# etc.net
KiCad netlist of a schematic drawn in Altium Designer
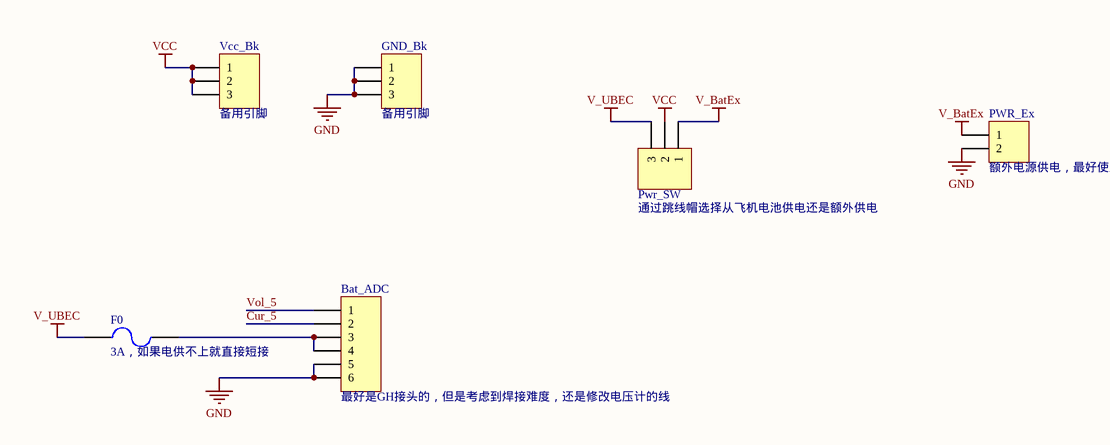
[diagram p0: etc.SchDoc]

(export (version "E")
  (design (tool "Eeschema 10.0.6"))
  (components
    (comp (ref "Bat_ADC")
      (value "最好是GH接头的，但是考虑到焊接难度，还是修改电压计的线")
      (footprint "HDR1X6")
      (description "Header, 6-Pin")
      (fields (field (name "PUBLISHER") "Altium Limited"))
      (libsource (lib "Miscellaneous Connectors") (part "Header 6"))
    )
    (comp (ref "F0")
      (value "3A，如果电供不上就直接短接")
      (footprint "Miscellaneous Devices:1812")
      (description "Fuse")
      (fields (field (name "PUBLISHER") "Altium Limited"))
      (libsource (lib "Miscellaneous Devices") (part "Fuse 2"))
    )
    (comp (ref "GND_Bk")
      (value "备用引脚")
      (footprint "HDR1X3")
      (description "Header, 3-Pin")
      (fields (field (name "PUBLISHER") "Altium Limited"))
      (libsource (lib "Miscellaneous Connectors") (part "Header 3"))
    )
    (comp (ref "PWR_Ex")
      (value "额外电源供电，最好使用接线端子")
      (footprint "HDR1X2")
      (description "Header, 2-Pin")
      (fields (field (name "PUBLISHER") "Altium Limited"))
      (libsource (lib "Miscellaneous Connectors") (part "Header 2"))
    )
    (comp (ref "Pwr_SW")
      (value "通过跳线帽选择从飞机电池供电还是额外供电")
      (footprint "HDR1X3")
      (description "Header, 3-Pin")
      (fields (field (name "PUBLISHER") "Altium Limited"))
      (libsource (lib "") (part "Header 3_1"))
    )
    (comp (ref "Vcc_Bk")
      (value "备用引脚")
      (footprint "HDR1X3")
      (description "Header, 3-Pin")
      (fields (field (name "PUBLISHER") "Altium Limited"))
      (libsource (lib "Miscellaneous Connectors") (part "Header 3"))
    )
  )
  (nets
    (net (code "1") (name "/Cur_5") (class "Default")
      (node (ref "Bat_ADC") (pin "2") (pinfunction "2_2") (pintype "passive"))
    )
    (net (code "2") (name "/Vol_5") (class "Default")
      (node (ref "Bat_ADC") (pin "1") (pinfunction "1_1") (pintype "passive"))
    )
    (net (code "3") (name "GND") (class "Default")
      (node (ref "Bat_ADC") (pin "5") (pinfunction "5_5") (pintype "passive"))
      (node (ref "Bat_ADC") (pin "6") (pinfunction "6_6") (pintype "passive"))
      (node (ref "GND_Bk") (pin "1") (pinfunction "1_1") (pintype "passive"))
      (node (ref "GND_Bk") (pin "2") (pinfunction "2_2") (pintype "passive"))
      (node (ref "GND_Bk") (pin "3") (pinfunction "3_3") (pintype "passive"))
      (node (ref "PWR_Ex") (pin "2") (pinfunction "2_2") (pintype "passive"))
    )
    (net (code "4") (name "Net-(Bat_ADC-Pad3)") (class "Default")
      (node (ref "Bat_ADC") (pin "3") (pinfunction "3_3") (pintype "passive"))
      (node (ref "Bat_ADC") (pin "4") (pinfunction "4_4") (pintype "passive"))
      (node (ref "F0") (pin "2") (pinfunction "2_2") (pintype "passive"))
    )
    (net (code "5") (name "VCC") (class "Default")
      (node (ref "Pwr_SW") (pin "2") (pinfunction "2_2") (pintype "passive"))
      (node (ref "Vcc_Bk") (pin "1") (pinfunction "1_1") (pintype "passive"))
      (node (ref "Vcc_Bk") (pin "2") (pinfunction "2_2") (pintype "passive"))
      (node (ref "Vcc_Bk") (pin "3") (pinfunction "3_3") (pintype "passive"))
    )
    (net (code "6") (name "V_BatEx") (class "Default")
      (node (ref "PWR_Ex") (pin "1") (pinfunction "1_1") (pintype "passive"))
      (node (ref "Pwr_SW") (pin "1") (pinfunction "1_1") (pintype "passive"))
    )
    (net (code "7") (name "V_UBEC") (class "Default")
      (node (ref "F0") (pin "1") (pinfunction "1_1") (pintype "passive"))
      (node (ref "Pwr_SW") (pin "3") (pinfunction "3_3") (pintype "passive"))
    )
  )
)
